# FrontboardTEST.net
KiCad netlist of a schematic drawn in EAGLE
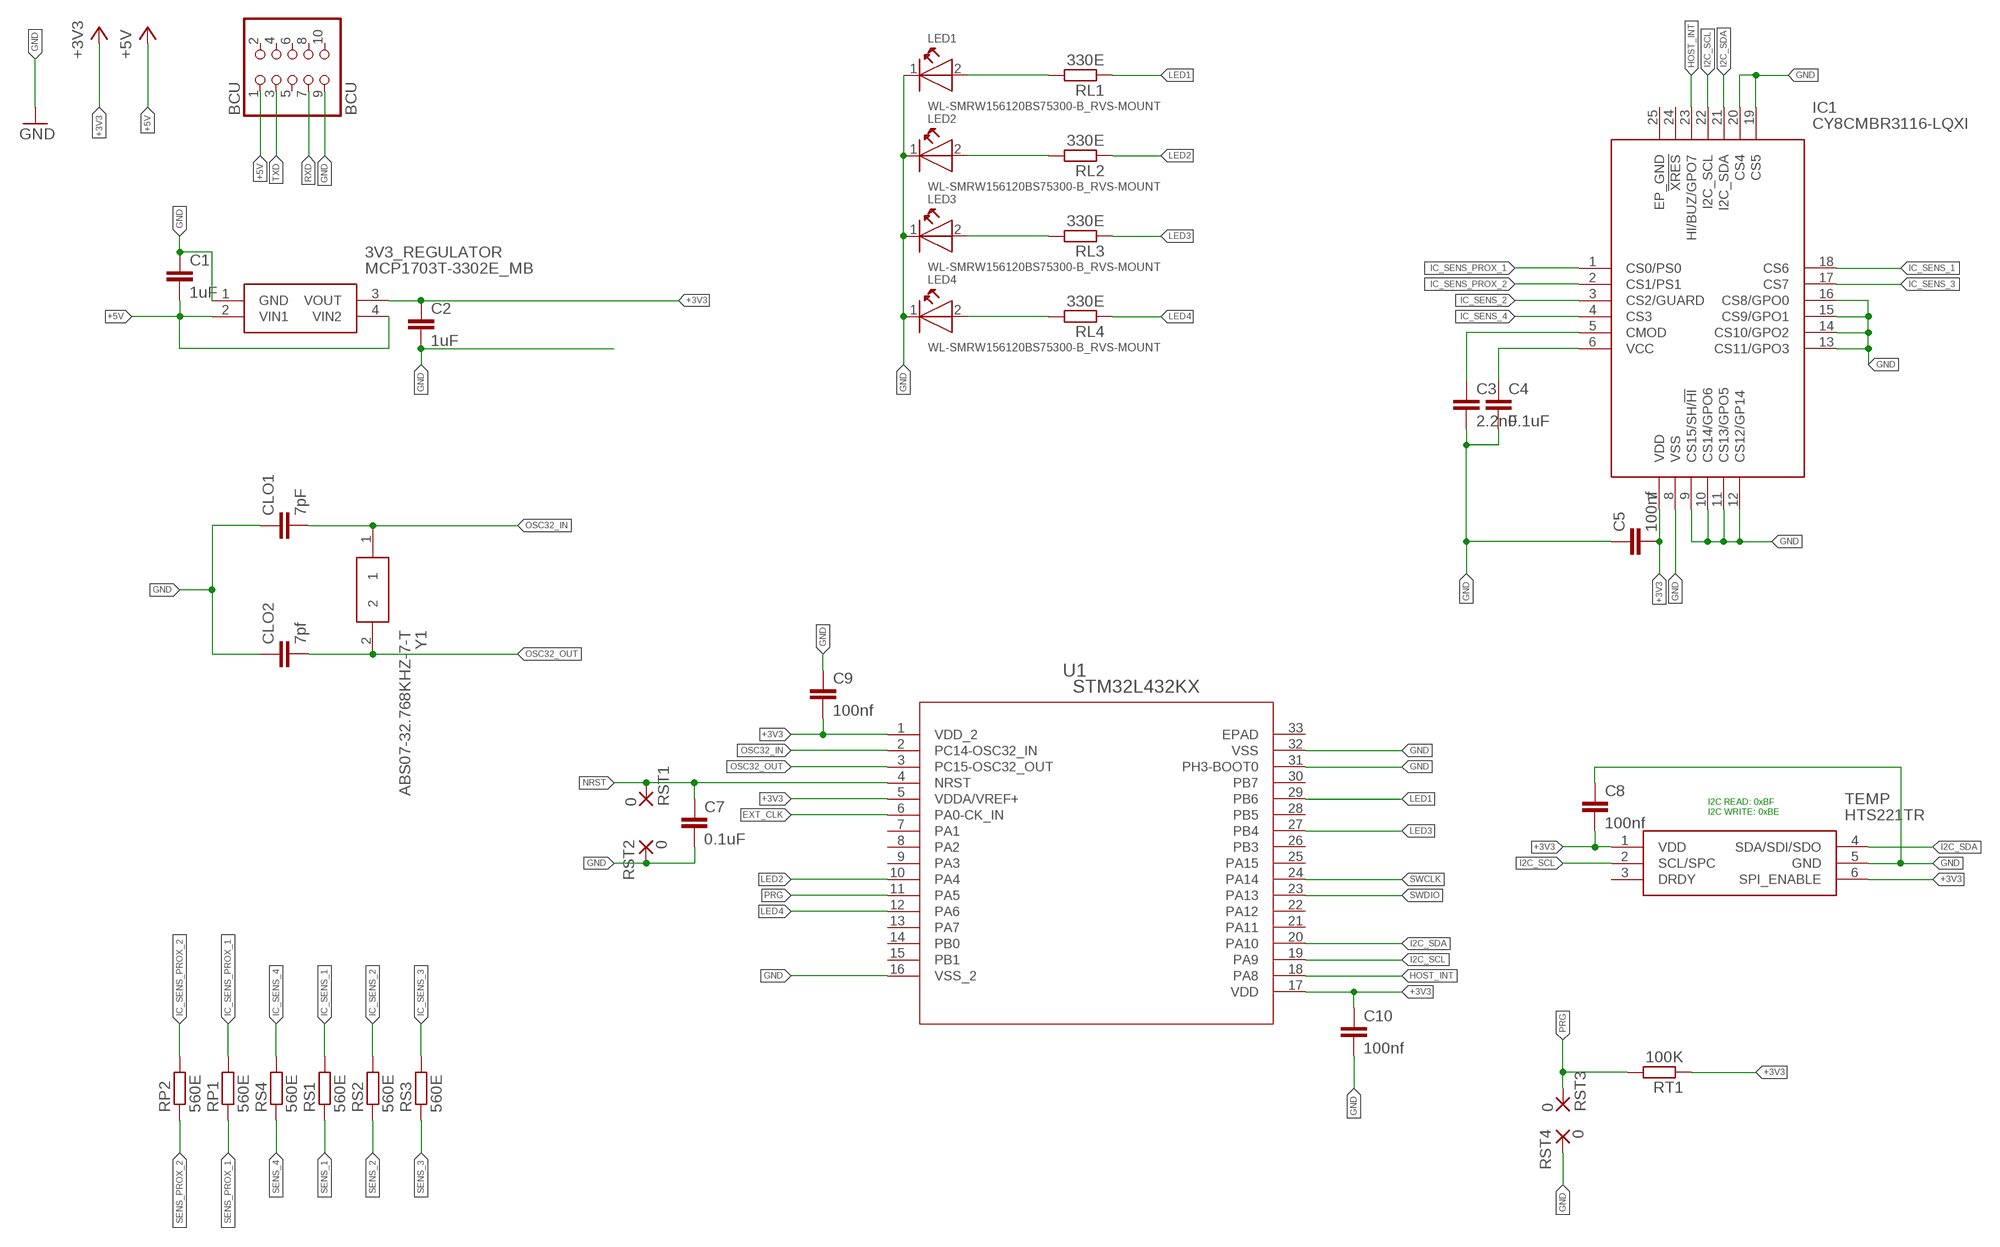
[diagram p0: schematic, sheet 1]

(export (version "E")
  (design (tool "Eeschema 10.0.6"))
  (components
    (comp (ref "3V3_REGULATOR")
      (value "MCP1703T-3302E_MB")
      (footprint "eagle-import:SOT-89(MB)")
      (fields
        (field (name "ARROW_PART_NUMBER") "MCP1703T-3302E/MB")
        (field (name "RS_PART_NUMBER") "9122916")
      )
      (libsource (lib "eagle-import") (part "MCP1703T-3302E_MB"))
    )
    (comp (ref "BCU")
      (value "BCU")
      (footprint "eagle-import:2X05SMD")
      (libsource (lib "eagle-import") (part "PINHD-2X5_2.54-SMD"))
    )
    (comp (ref "C1")
      (value "1uF")
      (footprint "eagle-import:C0603")
      (libsource (lib "eagle-import") (part "C-EUC0603"))
    )
    (comp (ref "C2")
      (value "1uF")
      (footprint "eagle-import:C0603")
      (libsource (lib "eagle-import") (part "C-EUC0603"))
    )
    (comp (ref "C3")
      (value "2.2nF")
      (footprint "eagle-import:C0603")
      (libsource (lib "eagle-import") (part "C-EUC0603"))
    )
    (comp (ref "C4")
      (value "0.1uF")
      (footprint "eagle-import:C0603")
      (libsource (lib "eagle-import") (part "C-EUC0603"))
    )
    (comp (ref "C5")
      (value "100nf")
      (footprint "eagle-import:C0603")
      (libsource (lib "eagle-import") (part "C-EUC0603"))
    )
    (comp (ref "C7")
      (value "0.1uF")
      (footprint "eagle-import:C0603")
      (libsource (lib "eagle-import") (part "C-EUC0603"))
    )
    (comp (ref "C8")
      (value "100nf")
      (footprint "eagle-import:C0603")
      (libsource (lib "eagle-import") (part "C-EUC0603"))
    )
    (comp (ref "C9")
      (value "100nf")
      (footprint "eagle-import:C0603")
      (libsource (lib "eagle-import") (part "C-EUC0603"))
    )
    (comp (ref "C10")
      (value "100nf")
      (footprint "eagle-import:C0603")
      (libsource (lib "eagle-import") (part "C-EUC0603"))
    )
    (comp (ref "CLO1")
      (value "7pF")
      (footprint "eagle-import:C0603")
      (libsource (lib "eagle-import") (part "C-EUC0603"))
    )
    (comp (ref "CLO2")
      (value "7pf")
      (footprint "eagle-import:C0603")
      (libsource (lib "eagle-import") (part "C-EUC0603"))
    )
    (comp (ref "IC1")
      (value "CY8CMBR3116-LQXI")
      (footprint "eagle-import:QFN50P400X400X60-25N")
      (fields (field (name "RS_PART_NUMBER") "1242976P"))
      (libsource (lib "eagle-import") (part "CY8CMBR3116-LQXI"))
    )
    (comp (ref "LED1")
      (value "WL-SMRW156120BS75300-B_RVS-MOUNT")
      (footprint "eagle-import:WL-SMRW-1206-CYLDR-REVERSE-MOUNT")
      (libsource (lib "eagle-import") (part "WL-SMRW156120BS75300-B_RVS-MOUNT"))
    )
    (comp (ref "LED2")
      (value "WL-SMRW156120BS75300-B_RVS-MOUNT")
      (footprint "eagle-import:WL-SMRW-1206-CYLDR-REVERSE-MOUNT")
      (libsource (lib "eagle-import") (part "WL-SMRW156120BS75300-B_RVS-MOUNT"))
    )
    (comp (ref "LED3")
      (value "WL-SMRW156120BS75300-B_RVS-MOUNT")
      (footprint "eagle-import:WL-SMRW-1206-CYLDR-REVERSE-MOUNT")
      (libsource (lib "eagle-import") (part "WL-SMRW156120BS75300-B_RVS-MOUNT"))
    )
    (comp (ref "LED4")
      (value "WL-SMRW156120BS75300-B_RVS-MOUNT")
      (footprint "eagle-import:WL-SMRW-1206-CYLDR-REVERSE-MOUNT")
      (libsource (lib "eagle-import") (part "WL-SMRW156120BS75300-B_RVS-MOUNT"))
    )
    (comp (ref "RL1")
      (value "330E")
      (footprint "eagle-import:R0603")
      (libsource (lib "eagle-import") (part "R-EU_R0603"))
    )
    (comp (ref "RL2")
      (value "330E")
      (footprint "eagle-import:R0603")
      (libsource (lib "eagle-import") (part "R-EU_R0603"))
    )
    (comp (ref "RL3")
      (value "330E")
      (footprint "eagle-import:R0603")
      (libsource (lib "eagle-import") (part "R-EU_R0603"))
    )
    (comp (ref "RL4")
      (value "330E")
      (footprint "eagle-import:R0603")
      (libsource (lib "eagle-import") (part "R-EU_R0603"))
    )
    (comp (ref "RP1")
      (value "560E")
      (footprint "eagle-import:R0603")
      (libsource (lib "eagle-import") (part "R-EU_R0603"))
    )
    (comp (ref "RP2")
      (value "560E")
      (footprint "eagle-import:R0603")
      (libsource (lib "eagle-import") (part "R-EU_R0603"))
    )
    (comp (ref "RS1")
      (value "560E")
      (footprint "eagle-import:R0603")
      (libsource (lib "eagle-import") (part "R-EU_R0603"))
    )
    (comp (ref "RS2")
      (value "560E")
      (footprint "eagle-import:R0603")
      (libsource (lib "eagle-import") (part "R-EU_R0603"))
    )
    (comp (ref "RS3")
      (value "560E")
      (footprint "eagle-import:R0603")
      (libsource (lib "eagle-import") (part "R-EU_R0603"))
    )
    (comp (ref "RS4")
      (value "560E")
      (footprint "eagle-import:R0603")
      (libsource (lib "eagle-import") (part "R-EU_R0603"))
    )
    (comp (ref "RST1")
      (value "0")
      (footprint "eagle-import:SMD2,54-5,08")
      (libsource (lib "eagle-import") (part "SMD5"))
    )
    (comp (ref "RST2")
      (value "0")
      (footprint "eagle-import:SMD2,54-5,08")
      (libsource (lib "eagle-import") (part "SMD5"))
    )
    (comp (ref "RST3")
      (value "0")
      (footprint "eagle-import:SMD2,54-5,08")
      (libsource (lib "eagle-import") (part "SMD5"))
    )
    (comp (ref "RST4")
      (value "0")
      (footprint "eagle-import:SMD2,54-5,08")
      (libsource (lib "eagle-import") (part "SMD5"))
    )
    (comp (ref "RT1")
      (value "100K")
      (footprint "eagle-import:R0603")
      (libsource (lib "eagle-import") (part "R-EU_R0603"))
    )
    (comp (ref "TEMP")
      (value "HTS221TR")
      (footprint "eagle-import:HLGA-6L")
      (fields (field (name "RS_PART_NUMBER") "1660935"))
      (libsource (lib "eagle-import") (part "HTS221TR"))
    )
    (comp (ref "U1")
      (value "STM32L432KX")
      (footprint "eagle-import:UFQFPN32-5X5MM")
      (fields (field (name "MANUFACTURER_PART_NUMBER") "stm32l432kx"))
      (libsource (lib "eagle-import") (part "STM32L432KX"))
    )
    (comp (ref "Y1")
      (value "ABS07-32.768KHZ-7-T")
      (footprint "eagle-import:ABS-07")
      (fields (field (name "RS_PART_NUMBER") "1712773P"))
      (libsource (lib "eagle-import") (part "ABS07-32.768KHZ-7-T"))
    )
  )
  (nets
    (net (code "1") (name "+3V3") (class "Default")
      (node (ref "3V3_REGULATOR") (pin "3") (pinfunction "VOUT_3") (pintype "bidirectional"))
      (node (ref "C10") (pin "1") (pinfunction "1_1") (pintype "passive"))
      (node (ref "C2") (pin "1") (pinfunction "1_1") (pintype "passive"))
      (node (ref "C5") (pin "2") (pinfunction "2_2") (pintype "passive"))
      (node (ref "C8") (pin "2") (pinfunction "2_2") (pintype "passive"))
      (node (ref "C9") (pin "2") (pinfunction "2_2") (pintype "passive"))
      (node (ref "IC1") (pin "7") (pinfunction "VDD_7") (pintype "power_in"))
      (node (ref "RT1") (pin "1") (pinfunction "1_1") (pintype "passive"))
      (node (ref "TEMP") (pin "1") (pinfunction "VDD_1") (pintype "bidirectional"))
      (node (ref "TEMP") (pin "6") (pinfunction "SPI_ENABLE_6") (pintype "bidirectional"))
      (node (ref "U1") (pin "1") (pinfunction "VDD_2_1") (pintype "power_in"))
      (node (ref "U1") (pin "17") (pinfunction "VDD_17") (pintype "power_in"))
      (node (ref "U1") (pin "5") (pinfunction "VDDA/VREF+_5") (pintype "power_in"))
    )
    (net (code "2") (name "+5V") (class "Default")
      (node (ref "3V3_REGULATOR") (pin "2") (pinfunction "VIN1_2") (pintype "bidirectional"))
      (node (ref "3V3_REGULATOR") (pin "4") (pinfunction "VIN2_4") (pintype "bidirectional"))
      (node (ref "BCU") (pin "1") (pinfunction "1_1") (pintype "passive"))
      (node (ref "C1") (pin "2") (pinfunction "2_2") (pintype "passive"))
    )
    (net (code "3") (name "/EP_GND") (class "Default")
      (node (ref "IC1") (pin "25") (pinfunction "EP_GND_25") (pintype "power_in"))
    )
    (net (code "4") (name "EXT_CLK") (class "Default")
      (node (ref "U1") (pin "6") (pinfunction "PA0-CK_IN_6") (pintype "bidirectional"))
    )
    (net (code "5") (name "GND") (class "Default")
      (node (ref "3V3_REGULATOR") (pin "1") (pinfunction "GND_1") (pintype "bidirectional"))
      (node (ref "BCU") (pin "9") (pinfunction "9_9") (pintype "passive"))
      (node (ref "C1") (pin "1") (pinfunction "1_1") (pintype "passive"))
      (node (ref "C10") (pin "2") (pinfunction "2_2") (pintype "passive"))
      (node (ref "C2") (pin "2") (pinfunction "2_2") (pintype "passive"))
      (node (ref "C3") (pin "2") (pinfunction "2_2") (pintype "passive"))
      (node (ref "C4") (pin "2") (pinfunction "2_2") (pintype "passive"))
      (node (ref "C5") (pin "1") (pinfunction "1_1") (pintype "passive"))
      (node (ref "C7") (pin "2") (pinfunction "2_2") (pintype "passive"))
      (node (ref "C8") (pin "1") (pinfunction "1_1") (pintype "passive"))
      (node (ref "C9") (pin "1") (pinfunction "1_1") (pintype "passive"))
      (node (ref "CLO1") (pin "1") (pinfunction "1_1") (pintype "passive"))
      (node (ref "CLO2") (pin "1") (pinfunction "1_1") (pintype "passive"))
      (node (ref "IC1") (pin "10") (pinfunction "CS14/GPO6_10") (pintype "input"))
      (node (ref "IC1") (pin "11") (pinfunction "CS13/GPO5_11") (pintype "input"))
      (node (ref "IC1") (pin "12") (pinfunction "CS12/GP14_12") (pintype "input"))
      (node (ref "IC1") (pin "13") (pinfunction "CS11/GPO3_13") (pintype "input"))
      (node (ref "IC1") (pin "14") (pinfunction "CS10/GPO2_14") (pintype "input"))
      (node (ref "IC1") (pin "15") (pinfunction "CS9/GPO1_15") (pintype "input"))
      (node (ref "IC1") (pin "16") (pinfunction "CS8/GPO0_16") (pintype "input"))
      (node (ref "IC1") (pin "19") (pinfunction "CS5_19") (pintype "input"))
      (node (ref "IC1") (pin "20") (pinfunction "CS4_20") (pintype "input"))
      (node (ref "IC1") (pin "8") (pinfunction "VSS_8") (pintype "power_in"))
      (node (ref "IC1") (pin "9") (pinfunction "CS15/SH/~{HI}_9") (pintype "input"))
      (node (ref "LED1") (pin "1") (pinfunction "K_1") (pintype "bidirectional"))
      (node (ref "LED2") (pin "1") (pinfunction "K_1") (pintype "bidirectional"))
      (node (ref "LED3") (pin "1") (pinfunction "K_1") (pintype "bidirectional"))
      (node (ref "LED4") (pin "1") (pinfunction "K_1") (pintype "bidirectional"))
      (node (ref "RST2") (pin "1") (pinfunction "P_1") (pintype "passive"))
      (node (ref "RST4") (pin "1") (pinfunction "P_1") (pintype "passive"))
      (node (ref "TEMP") (pin "5") (pinfunction "GND_5") (pintype "bidirectional"))
      (node (ref "U1") (pin "16") (pinfunction "VSS_2_16") (pintype "power_in"))
      (node (ref "U1") (pin "31") (pinfunction "PH3-BOOT0_31") (pintype "bidirectional"))
      (node (ref "U1") (pin "32") (pinfunction "VSS_32") (pintype "power_in"))
    )
    (net (code "6") (name "HOST_INT") (class "Default")
      (node (ref "IC1") (pin "23") (pinfunction "HI/BUZ/GPO7_23") (pintype "bidirectional"))
      (node (ref "U1") (pin "18") (pinfunction "PA8_18") (pintype "bidirectional"))
    )
    (net (code "7") (name "I2C_SCL") (class "Default")
      (node (ref "IC1") (pin "22") (pinfunction "I2C_SCL_22") (pintype "bidirectional"))
      (node (ref "TEMP") (pin "2") (pinfunction "SCL/SPC_2") (pintype "bidirectional"))
      (node (ref "U1") (pin "19") (pinfunction "PA9_19") (pintype "bidirectional"))
    )
    (net (code "8") (name "I2C_SDA") (class "Default")
      (node (ref "IC1") (pin "21") (pinfunction "I2C_SDA_21") (pintype "bidirectional"))
      (node (ref "TEMP") (pin "4") (pinfunction "SDA/SDI/SDO_4") (pintype "bidirectional"))
      (node (ref "U1") (pin "20") (pinfunction "PA10_20") (pintype "bidirectional"))
    )
    (net (code "9") (name "IC_SENS_1") (class "Default")
      (node (ref "IC1") (pin "18") (pinfunction "CS6_18") (pintype "input"))
      (node (ref "RS1") (pin "2") (pinfunction "2_2") (pintype "passive"))
    )
    (net (code "10") (name "IC_SENS_2") (class "Default")
      (node (ref "IC1") (pin "3") (pinfunction "CS2/GUARD_3") (pintype "input"))
      (node (ref "RS2") (pin "2") (pinfunction "2_2") (pintype "passive"))
    )
    (net (code "11") (name "IC_SENS_3") (class "Default")
      (node (ref "IC1") (pin "17") (pinfunction "CS7_17") (pintype "input"))
      (node (ref "RS3") (pin "2") (pinfunction "2_2") (pintype "passive"))
    )
    (net (code "12") (name "IC_SENS_4") (class "Default")
      (node (ref "IC1") (pin "4") (pinfunction "CS3_4") (pintype "input"))
      (node (ref "RS4") (pin "2") (pinfunction "2_2") (pintype "passive"))
    )
    (net (code "13") (name "IC_SENS_PROX_1") (class "Default")
      (node (ref "IC1") (pin "1") (pinfunction "CS0/PS0_1") (pintype "input"))
      (node (ref "RP1") (pin "2") (pinfunction "2_2") (pintype "passive"))
    )
    (net (code "14") (name "IC_SENS_PROX_2") (class "Default")
      (node (ref "IC1") (pin "2") (pinfunction "CS1/PS1_2") (pintype "input"))
      (node (ref "RP2") (pin "2") (pinfunction "2_2") (pintype "passive"))
    )
    (net (code "15") (name "LED1") (class "Default")
      (node (ref "RL1") (pin "1") (pinfunction "1_1") (pintype "passive"))
      (node (ref "U1") (pin "29") (pinfunction "PB6_29") (pintype "bidirectional"))
    )
    (net (code "16") (name "LED2") (class "Default")
      (node (ref "RL2") (pin "1") (pinfunction "1_1") (pintype "passive"))
      (node (ref "U1") (pin "10") (pinfunction "PA4_10") (pintype "bidirectional"))
    )
    (net (code "17") (name "LED3") (class "Default")
      (node (ref "RL3") (pin "1") (pinfunction "1_1") (pintype "passive"))
      (node (ref "U1") (pin "27") (pinfunction "PB4_27") (pintype "bidirectional"))
    )
    (net (code "18") (name "LED4") (class "Default")
      (node (ref "RL4") (pin "1") (pinfunction "1_1") (pintype "passive"))
      (node (ref "U1") (pin "12") (pinfunction "PA6_12") (pintype "bidirectional"))
    )
    (net (code "19") (name "NRST") (class "Default")
      (node (ref "C7") (pin "1") (pinfunction "1_1") (pintype "passive"))
      (node (ref "RST1") (pin "1") (pinfunction "P_1") (pintype "passive"))
      (node (ref "U1") (pin "4") (pinfunction "NRST_4") (pintype "bidirectional"))
    )
    (net (code "20") (name "Net-(IC1-CMOD)") (class "Default")
      (node (ref "C3") (pin "1") (pinfunction "1_1") (pintype "passive"))
      (node (ref "IC1") (pin "5") (pinfunction "CMOD_5") (pintype "bidirectional"))
    )
    (net (code "21") (name "Net-(IC1-VCC)") (class "Default")
      (node (ref "C4") (pin "1") (pinfunction "1_1") (pintype "passive"))
      (node (ref "IC1") (pin "6") (pinfunction "VCC_6") (pintype "power_in"))
    )
    (net (code "22") (name "Net-(LED1-A)") (class "Default")
      (node (ref "LED1") (pin "2") (pinfunction "A_2") (pintype "bidirectional"))
      (node (ref "RL1") (pin "2") (pinfunction "2_2") (pintype "passive"))
    )
    (net (code "23") (name "Net-(LED2-A)") (class "Default")
      (node (ref "LED2") (pin "2") (pinfunction "A_2") (pintype "bidirectional"))
      (node (ref "RL2") (pin "2") (pinfunction "2_2") (pintype "passive"))
    )
    (net (code "24") (name "Net-(LED3-A)") (class "Default")
      (node (ref "LED3") (pin "2") (pinfunction "A_2") (pintype "bidirectional"))
      (node (ref "RL3") (pin "2") (pinfunction "2_2") (pintype "passive"))
    )
    (net (code "25") (name "Net-(LED4-A)") (class "Default")
      (node (ref "LED4") (pin "2") (pinfunction "A_2") (pintype "bidirectional"))
      (node (ref "RL4") (pin "2") (pinfunction "2_2") (pintype "passive"))
    )
    (net (code "26") (name "OSC32_IN") (class "Default")
      (node (ref "CLO1") (pin "2") (pinfunction "2_2") (pintype "passive"))
      (node (ref "U1") (pin "2") (pinfunction "PC14-OSC32_IN_2") (pintype "bidirectional"))
      (node (ref "Y1") (pin "1") (pinfunction "1_1") (pintype "bidirectional"))
    )
    (net (code "27") (name "OSC32_OUT") (class "Default")
      (node (ref "CLO2") (pin "2") (pinfunction "2_2") (pintype "passive"))
      (node (ref "U1") (pin "3") (pinfunction "PC15-OSC32_OUT_3") (pintype "bidirectional"))
      (node (ref "Y1") (pin "2") (pinfunction "2_2") (pintype "bidirectional"))
    )
    (net (code "28") (name "PRG") (class "Default")
      (node (ref "RST3") (pin "1") (pinfunction "P_1") (pintype "passive"))
      (node (ref "RT1") (pin "2") (pinfunction "2_2") (pintype "passive"))
      (node (ref "U1") (pin "11") (pinfunction "PA5_11") (pintype "bidirectional"))
    )
    (net (code "29") (name "RXD") (class "Default")
      (node (ref "BCU") (pin "7") (pinfunction "7_7") (pintype "passive"))
    )
    (net (code "30") (name "SENS_1") (class "Default")
      (node (ref "RS1") (pin "1") (pinfunction "1_1") (pintype "passive"))
    )
    (net (code "31") (name "SENS_2") (class "Default")
      (node (ref "RS2") (pin "1") (pinfunction "1_1") (pintype "passive"))
    )
    (net (code "32") (name "SENS_3") (class "Default")
      (node (ref "RS3") (pin "1") (pinfunction "1_1") (pintype "passive"))
    )
    (net (code "33") (name "SENS_4") (class "Default")
      (node (ref "RS4") (pin "1") (pinfunction "1_1") (pintype "passive"))
    )
    (net (code "34") (name "SENS_PROX_1") (class "Default")
      (node (ref "RP1") (pin "1") (pinfunction "1_1") (pintype "passive"))
    )
    (net (code "35") (name "SENS_PROX_2") (class "Default")
      (node (ref "RP2") (pin "1") (pinfunction "1_1") (pintype "passive"))
    )
    (net (code "36") (name "SWCLK") (class "Default")
      (node (ref "U1") (pin "24") (pinfunction "PA14_24") (pintype "bidirectional"))
    )
    (net (code "37") (name "SWDIO") (class "Default")
      (node (ref "U1") (pin "23") (pinfunction "PA13_23") (pintype "bidirectional"))
    )
    (net (code "38") (name "TXD") (class "Default")
      (node (ref "BCU") (pin "3") (pinfunction "3_3") (pintype "passive"))
    )
    (net (code "39") (name "unconnected-(BCU-Pad2)") (class "Default")
      (node (ref "BCU") (pin "2") (pinfunction "2_2") (pintype "passive"))
    )
    (net (code "40") (name "unconnected-(BCU-Pad4)") (class "Default")
      (node (ref "BCU") (pin "4") (pinfunction "4_4") (pintype "passive"))
    )
    (net (code "41") (name "unconnected-(BCU-Pad5)") (class "Default")
      (node (ref "BCU") (pin "5") (pinfunction "5_5") (pintype "passive"))
    )
    (net (code "42") (name "unconnected-(BCU-Pad6)") (class "Default")
      (node (ref "BCU") (pin "6") (pinfunction "6_6") (pintype "passive"))
    )
    (net (code "43") (name "unconnected-(BCU-Pad8)") (class "Default")
      (node (ref "BCU") (pin "8") (pinfunction "8_8") (pintype "passive"))
    )
    (net (code "44") (name "unconnected-(BCU-Pad10)") (class "Default")
      (node (ref "BCU") (pin "10") (pinfunction "10_10") (pintype "passive"))
    )
    (net (code "45") (name "unconnected-(IC1-~{XRES}-Pad24)") (class "Default")
      (node (ref "IC1") (pin "24") (pinfunction "~{XRES}_24") (pintype "bidirectional"))
    )
    (net (code "46") (name "unconnected-(TEMP-DRDY-Pad3)") (class "Default")
      (node (ref "TEMP") (pin "3") (pinfunction "DRDY_3") (pintype "bidirectional"))
    )
    (net (code "47") (name "unconnected-(U1-EPAD-Pad33)") (class "Default")
      (node (ref "U1") (pin "33") (pinfunction "EPAD_33") (pintype "passive"))
    )
    (net (code "48") (name "unconnected-(U1-PA1-Pad7)") (class "Default")
      (node (ref "U1") (pin "7") (pinfunction "PA1_7") (pintype "bidirectional"))
    )
    (net (code "49") (name "unconnected-(U1-PA2-Pad8)") (class "Default")
      (node (ref "U1") (pin "8") (pinfunction "PA2_8") (pintype "bidirectional"))
    )
    (net (code "50") (name "unconnected-(U1-PA3-Pad9)") (class "Default")
      (node (ref "U1") (pin "9") (pinfunction "PA3_9") (pintype "bidirectional"))
    )
    (net (code "51") (name "unconnected-(U1-PA7-Pad13)") (class "Default")
      (node (ref "U1") (pin "13") (pinfunction "PA7_13") (pintype "bidirectional"))
    )
    (net (code "52") (name "unconnected-(U1-PA11-Pad21)") (class "Default")
      (node (ref "U1") (pin "21") (pinfunction "PA11_21") (pintype "bidirectional"))
    )
    (net (code "53") (name "unconnected-(U1-PA12-Pad22)") (class "Default")
      (node (ref "U1") (pin "22") (pinfunction "PA12_22") (pintype "bidirectional"))
    )
    (net (code "54") (name "unconnected-(U1-PA15-Pad25)") (class "Default")
      (node (ref "U1") (pin "25") (pinfunction "PA15_25") (pintype "bidirectional"))
    )
    (net (code "55") (name "unconnected-(U1-PB0-Pad14)") (class "Default")
      (node (ref "U1") (pin "14") (pinfunction "PB0_14") (pintype "bidirectional"))
    )
    (net (code "56") (name "unconnected-(U1-PB1-Pad15)") (class "Default")
      (node (ref "U1") (pin "15") (pinfunction "PB1_15") (pintype "bidirectional"))
    )
    (net (code "57") (name "unconnected-(U1-PB3-Pad26)") (class "Default")
      (node (ref "U1") (pin "26") (pinfunction "PB3_26") (pintype "bidirectional"))
    )
    (net (code "58") (name "unconnected-(U1-PB5-Pad28)") (class "Default")
      (node (ref "U1") (pin "28") (pinfunction "PB5_28") (pintype "bidirectional"))
    )
    (net (code "59") (name "unconnected-(U1-PB7-Pad30)") (class "Default")
      (node (ref "U1") (pin "30") (pinfunction "PB7_30") (pintype "bidirectional"))
    )
  )
)
